# Buck_Converter.net
KiCad netlist of a schematic drawn in Altium Designer
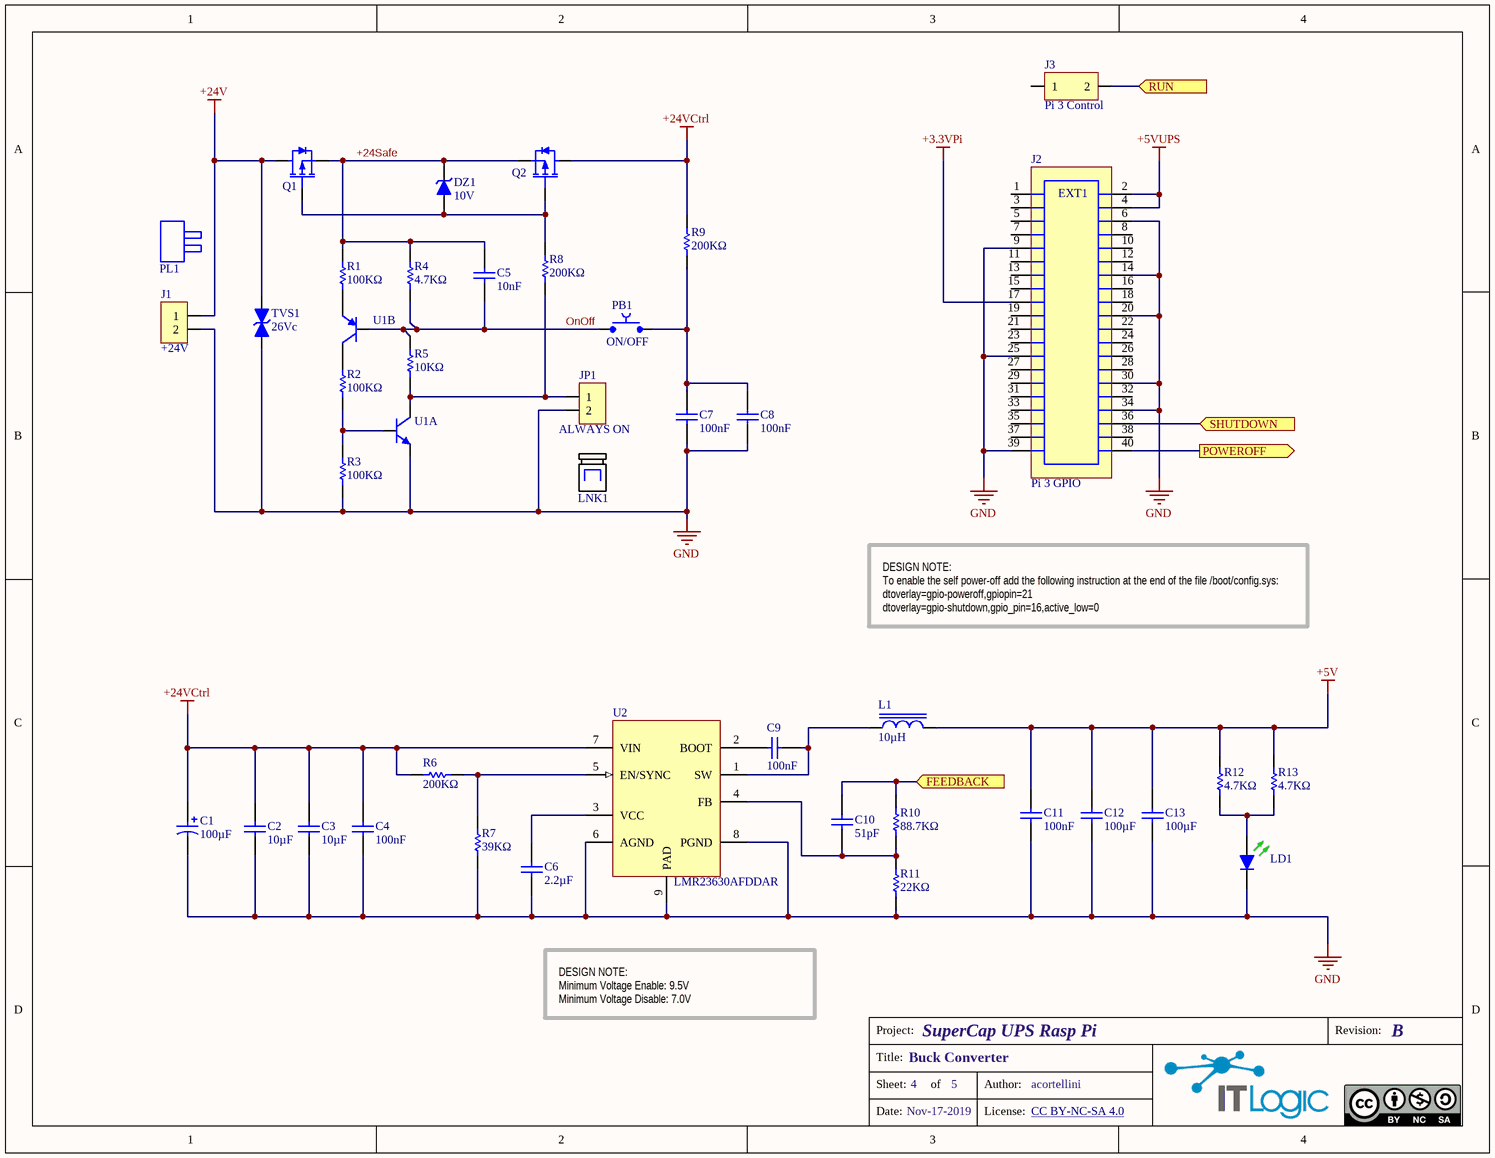
[diagram p0: Buck Converter.SchDoc]

(export (version "E")
  (design (tool "Eeschema 10.0.6"))
  (components
    (comp (ref "C1")
      (value "100µF")
      (footprint "C-AE-C6-H60")
      (description "Cap Electrolytic Alu 100uF 300V 20% (5.8 X 6.1mm) SMD 600mA 2000h 105C")
      (fields
        (field (name "MANUFACTURER") "Panasonic")
        (field (name "MANUFACTURER PART NUMBER") "EEE-FT1V101AP")
      )
      (libsource (lib "IT Logic Library") (part "EEE-FT1V101AP"))
    )
    (comp (ref "C2")
      (value "10µF")
      (footprint "C1206-H180")
      (description "Cap 1206 Case Ceramic 10uF 50V X5S 20%")
      (fields
        (field (name "MANUFACTURER") "Murata")
        (field (name "MANUFACTURER PART NUMBER") "GRT31CR61H106ME01L")
      )
      (libsource (lib "IT Logic Library") (part "GRT31CR61H106ME01L"))
    )
    (comp (ref "C3")
      (value "10µF")
      (footprint "C1206-H180")
      (description "Cap 1206 Case Ceramic 10uF 50V X5S 20%")
      (fields
        (field (name "MANUFACTURER") "Murata")
        (field (name "MANUFACTURER PART NUMBER") "GRT31CR61H106ME01L")
      )
      (libsource (lib "IT Logic Library") (part "GRT31CR61H106ME01L"))
    )
    (comp (ref "C4")
      (value "100nF")
      (footprint "C0805-H10")
      (description "Cap 0805 Case Ceramic 100nF 50V X7R")
      (fields
        (field (name "MANUFACTURER") "KEMET")
        (field (name "MANUFACTURER PART NUMBER") "C0805C104K5RACTU")
      )
      (libsource (lib "IT Logic Library") (part "C0805C104K5RACTU"))
    )
    (comp (ref "C5")
      (value "10nF")
      (footprint "C0805-H10")
      (description "Cap 0805 Case Ceramic 10nF 50V X7R")
      (fields
        (field (name "MANUFACTURER") "KEMET")
        (field (name "MANUFACTURER PART NUMBER") "C0805C103K5RACTU")
      )
      (libsource (lib "IT Logic Library") (part "C0805C103K5RACTU"))
    )
    (comp (ref "C6")
      (value "2.2µF")
      (footprint "C0805-H140")
      (description "Cap 0805 Case Ceramic 2.2uF 16V X7R 10%")
      (fields
        (field (name "MANUFACTURER") "KEMET")
        (field (name "MANUFACTURER PART NUMBER") "C0805C225K4RACTU")
      )
      (libsource (lib "IT Logic Library") (part "C0805C225K4RACTU"))
    )
    (comp (ref "C7")
      (value "100nF")
      (footprint "C0805-H10")
      (description "Cap 0805 Case Ceramic 100nF 50V X7R")
      (fields
        (field (name "MANUFACTURER") "KEMET")
        (field (name "MANUFACTURER PART NUMBER") "C0805C104K5RACTU")
      )
      (libsource (lib "IT Logic Library") (part "C0805C104K5RACTU"))
    )
    (comp (ref "C8")
      (value "100nF")
      (footprint "C0805-H10")
      (description "Cap 0805 Case Ceramic 100nF 50V X7R")
      (fields
        (field (name "MANUFACTURER") "KEMET")
        (field (name "MANUFACTURER PART NUMBER") "C0805C104K5RACTU")
      )
      (libsource (lib "IT Logic Library") (part "C0805C104K5RACTU"))
    )
    (comp (ref "C9")
      (value "100nF")
      (footprint "C0805-H10")
      (description "Cap 0805 Case Ceramic 100nF 50V X7R")
      (fields
        (field (name "MANUFACTURER") "KEMET")
        (field (name "MANUFACTURER PART NUMBER") "C0805C104K5RACTU")
      )
      (libsource (lib "IT Logic Library") (part "C0805C104K5RACTU"))
    )
    (comp (ref "C10")
      (value "51pF")
      (footprint "C0805-H10")
      (description "Cap 0805 Case Ceramic 51pF 50V C0G 10%")
      (fields
        (field (name "MANUFACTURER") "KEMET")
        (field (name "MANUFACTURER PART NUMBER") "C0805C510K5GACTU")
      )
      (libsource (lib "IT Logic Library") (part "C0805C510K5GACTU"))
    )
    (comp (ref "C11")
      (value "100nF")
      (footprint "C0805-H10")
      (description "Cap 0805 Case Ceramic 100nF 50V X7R")
      (fields
        (field (name "MANUFACTURER") "KEMET")
        (field (name "MANUFACTURER PART NUMBER") "C0805C104K5RACTU")
      )
      (libsource (lib "IT Logic Library") (part "C0805C104K5RACTU"))
    )
    (comp (ref "C12")
      (value "100µF")
      (footprint "C1210-H250")
      (description "Cap 1210 Case Ceramic 100uF 10V X5S 20%")
      (fields
        (field (name "MANUFACTURER") "Murata")
        (field (name "MANUFACTURER PART NUMBER") "GRM32ER61A107ME20L")
      )
      (libsource (lib "IT Logic Library") (part "GRM32ER61A107ME20L"))
    )
    (comp (ref "C13")
      (value "100µF")
      (footprint "C1210-H250")
      (description "Cap 1210 Case Ceramic 100uF 10V X5S 20%")
      (fields
        (field (name "MANUFACTURER") "Murata")
        (field (name "MANUFACTURER PART NUMBER") "GRM32ER61A107ME20L")
      )
      (libsource (lib "IT Logic Library") (part "GRM32ER61A107ME20L"))
    )
    (comp (ref "DZ1")
      (value "10V")
      (footprint "SOD-123")
      (description "Diode Zener Single 10V 5% 400mW SOD-123")
      (fields
        (field (name "MANUFACTURER") "Vishay Semiconductors")
        (field (name "MANUFACTURER PART NUMBER") "BZT52C10-E3-08")
      )
      (libsource (lib "IT Logic Library") (part "BZT52C10-E3-08"))
    )
    (comp (ref "EXT1")
      (value "SSQ-120-03-T-D-MEC")
      (footprint "SSQ-120-03-D-BOTTOM")
      (description "Conn Post Socket Header Vert - 2 Row - 20 Pos - 10 mm Lenght - Tin")
      (fields
        (field (name "MANUFACTURER") "Samtec")
        (field (name "MANUFACTURER PART NUMBER") "SSQ-120-03-T-D")
      )
      (libsource (lib "IT Logic Library") (part "SSQ-120-03-T-D-MEC"))
    )
    (comp (ref "J1")
      (value "+24V")
      (footprint "691322110002")
      (description "Conn Term Block Header 2 Pos 3.5 mm")
      (fields
        (field (name "MANUFACTURER") "Wurth Electronics")
        (field (name "MANUFACTURER PART NUMBER") "691322110002")
      )
      (libsource (lib "IT Logic Library") (part "691322110002"))
    )
    (comp (ref "J2")
      (value "Pi 3 GPIO")
      (footprint "HLE-120-02-F-DV-BE")
      (description "Conn Socket Header Vert - 2 Row - 20 Pos - SMD")
      (fields
        (field (name "MANUFACTURER") "Samtec")
        (field (name "MANUFACTURER PART NUMBER") "HLE-120-02-F-DV-BE")
      )
      (libsource (lib "IT Logic Library") (part "HLE-120-02-F-DV-BE"))
    )
    (comp (ref "J3")
      (value "Pi 3 Control")
      (footprint "SSQ-102-01-S-BOTTOM")
      (description "Conn Post Socket Header Vert - 1 Row - 2 Pos - 3 mm Lenght - Tin")
      (fields
        (field (name "MANUFACTURER") "Samtec")
        (field (name "MANUFACTURER PART NUMBER") "SSQ-102-01-T-S")
      )
      (libsource (lib "IT Logic Library") (part "SSQ-102-01-T-S"))
    )
    (comp (ref "JP1")
      (value "ALWAYS ON")
      (footprint "HDR-V-1R-02P-5.8L")
      (description "Breakaway Header Vert - 1 Row - 2 Pos - 6 mm Lenght - Gold")
      (fields (field (name "MANUFACTURER") "Molex") (field (name "MANUFACTURER PART NUMBER") "22-28-4023"))
      (libsource (lib "IT Logic Library") (part "22-28-4023"))
    )
    (comp (ref "L1")
      (value "10µH")
      (footprint "IND-XAL6060")
      (description "Inductor Power XAL60 Series, 10uH, 7.6A,  Shielded, 27 mOhm, SMD")
      (fields
        (field (name "MANUFACTURER") "Coilcraft")
        (field (name "MANUFACTURER PART NUMBER") "XAL6060-103MEB")
      )
      (libsource (lib "IT Logic Library") (part "XAL6060-103MEB"))
    )
    (comp (ref "LD1")
      (value "LTST-S220KGKT")
      (footprint "LED-0805-G-SIDE")
      (description "LED 0805 Side Green 569nm 2-Pin")
      (fields (field (name "MANUFACTURER") "Vishay Lite-On"))
      (libsource (lib "IT Logic Library") (part "LTST-S220KGKT"))
    )
    (comp (ref "LNK1")
      (value "2-881545-2")
      (description "Jumper Red, 2 Pos, 2.54 pitch")
      (fields (field (name "MANUFACTURER") "TE Connectivity"))
      (libsource (lib "IT Logic Library") (part "2-881545-2"))
    )
    (comp (ref "PB1")
      (value "ON/OFF")
      (footprint "BUT-1-1825027-4")
      (description "Tactile Switch, Round Stem, Color ivory, Lenght 3.55mm, Right Angle, Through Hole.")
      (fields
        (field (name "MANUFACTURER") "TE Connectivity")
        (field (name "MANUFACTURER PART NUMBER") "1-1825027-4")
      )
      (libsource (lib "IT Logic Library") (part "1-1825027-4"))
    )
    (comp (ref "PL1")
      (value "691361100002")
      (description "Conn Term Block Plug Vert 2 Pos 3.5 mm")
      (fields (field (name "MANUFACTURER") "Wurth Electronics"))
      (libsource (lib "IT Logic Library") (part "691361100002"))
    )
    (comp (ref "Q1")
      (value "DMP6023LFG")
      (footprint "PowerDI3333-8-S")
      (description "Mosfet P 60V Vds 20V Vgs 25mOhm PowerDI3333-8")
      (fields (field (name "MANUFACTURER") "Diodes Incorporated"))
      (libsource (lib "IT Logic Library") (part "DMP6023LFG"))
    )
    (comp (ref "Q2")
      (value "DMP6023LFG")
      (footprint "PowerDI3333-8-S")
      (description "Mosfet P 60V Vds 20V Vgs 25mOhm PowerDI3333-8")
      (fields (field (name "MANUFACTURER") "Diodes Incorporated"))
      (libsource (lib "IT Logic Library") (part "DMP6023LFG"))
    )
    (comp (ref "R1")
      (value "100KΩ")
      (footprint "R0805-H60")
      (description "Resistor 0805 Case 100KR 1% 1/8W")
      (fields
        (field (name "MANUFACTURER") "Yageo")
        (field (name "MANUFACTURER PART NUMBER") "RC0805FR-07100KL")
      )
      (libsource (lib "IT Logic Library") (part "RC0805FR-07100KL"))
    )
    (comp (ref "R2")
      (value "100KΩ")
      (footprint "R0805-H60")
      (description "Resistor 0805 Case 100KR 1% 1/8W")
      (fields
        (field (name "MANUFACTURER") "Yageo")
        (field (name "MANUFACTURER PART NUMBER") "RC0805FR-07100KL")
      )
      (libsource (lib "IT Logic Library") (part "RC0805FR-07100KL"))
    )
    (comp (ref "R3")
      (value "100KΩ")
      (footprint "R0805-H60")
      (description "Resistor 0805 Case 100KR 1% 1/8W")
      (fields
        (field (name "MANUFACTURER") "Yageo")
        (field (name "MANUFACTURER PART NUMBER") "RC0805FR-07100KL")
      )
      (libsource (lib "IT Logic Library") (part "RC0805FR-07100KL"))
    )
    (comp (ref "R4")
      (value "4.7KΩ")
      (footprint "R0805-H60")
      (description "Resistor 0805 Case 4.7KR 1% 1/8W")
      (fields
        (field (name "MANUFACTURER") "Yageo")
        (field (name "MANUFACTURER PART NUMBER") "RC0805FR-074K7L")
      )
      (libsource (lib "IT Logic Library") (part "RC0805FR-074K7L"))
    )
    (comp (ref "R5")
      (value "10KΩ")
      (footprint "R0805-H60")
      (description "Resistor 0805 Case 10KR 1% 1/8W")
      (fields
        (field (name "MANUFACTURER") "Yageo")
        (field (name "MANUFACTURER PART NUMBER") "RC0805FR-0710KL")
      )
      (libsource (lib "IT Logic Library") (part "RC0805FR-0710KL"))
    )
    (comp (ref "R6")
      (value "200KΩ")
      (footprint "R0805-H60")
      (description "Resistor 0805 Case 200KR 1% 1/8W")
      (fields
        (field (name "MANUFACTURER") "Yageo")
        (field (name "MANUFACTURER PART NUMBER") "RC0805FR-07200KL")
      )
      (libsource (lib "IT Logic Library") (part "RC0805FR-07200KL"))
    )
    (comp (ref "R7")
      (value "39KΩ")
      (footprint "R0805-H60")
      (description "Resistor 0805 Case 39KR 1% 1/8W")
      (fields
        (field (name "MANUFACTURER") "Yageo")
        (field (name "MANUFACTURER PART NUMBER") "RC0805FR-0739KL")
      )
      (libsource (lib "IT Logic Library") (part "RC0805FR-0739KL"))
    )
    (comp (ref "R8")
      (value "200KΩ")
      (footprint "R0805-H60")
      (description "Resistor 0805 Case 200KR 1% 1/8W")
      (fields
        (field (name "MANUFACTURER") "Yageo")
        (field (name "MANUFACTURER PART NUMBER") "RC0805FR-07200KL")
      )
      (libsource (lib "IT Logic Library") (part "RC0805FR-07200KL"))
    )
    (comp (ref "R9")
      (value "200KΩ")
      (footprint "R0805-H60")
      (description "Resistor 0805 Case 200KR 1% 1/8W")
      (fields
        (field (name "MANUFACTURER") "Yageo")
        (field (name "MANUFACTURER PART NUMBER") "RC0805FR-07200KL")
      )
      (libsource (lib "IT Logic Library") (part "RC0805FR-07200KL"))
    )
    (comp (ref "R10")
      (value "88.7KΩ")
      (footprint "R0805-H60")
      (description "Resistor 0805 Case 88.7KR 1% 1/8W")
      (fields
        (field (name "MANUFACTURER") "Yageo")
        (field (name "MANUFACTURER PART NUMBER") "RC0805FR-0788K7L")
      )
      (libsource (lib "IT Logic Library") (part "RC0805FR-0788K7L"))
    )
    (comp (ref "R11")
      (value "22KΩ")
      (footprint "R0805-H60")
      (description "Resistor 0805 Case 22KR 1% 1/8W")
      (fields
        (field (name "MANUFACTURER") "Yageo")
        (field (name "MANUFACTURER PART NUMBER") "RC0805FR-0722KL")
      )
      (libsource (lib "IT Logic Library") (part "RC0805FR-0722KL"))
    )
    (comp (ref "R12")
      (value "4.7KΩ")
      (footprint "R0805-H60")
      (description "Resistor 0805 Case 4.7KR 1% 1/8W")
      (fields
        (field (name "MANUFACTURER") "Yageo")
        (field (name "MANUFACTURER PART NUMBER") "RC0805FR-074K7L")
      )
      (libsource (lib "IT Logic Library") (part "RC0805FR-074K7L"))
    )
    (comp (ref "R13")
      (value "4.7KΩ")
      (footprint "R0805-H60")
      (description "Resistor 0805 Case 4.7KR 1% 1/8W")
      (fields
        (field (name "MANUFACTURER") "Yageo")
        (field (name "MANUFACTURER PART NUMBER") "RC0805FR-074K7L")
      )
      (libsource (lib "IT Logic Library") (part "RC0805FR-074K7L"))
    )
    (comp (ref "TVS1")
      (value "26Vc")
      (footprint "DO-214AC-SMA-NO POL")
      (description "TVS Diode Bidirectional 26Vs, 42.1Vc, 9.5 Amp, SMA")
      (fields (field (name "MANUFACTURER") "Littelfuse") (field (name "MANUFACTURER PART NUMBER") "SMAJ26CA"))
      (libsource (lib "IT Logic Library") (part "SMAJ26CA"))
    )
    (comp (ref "U1")
      (value "MBT3946DW1T1G")
      (footprint "SOT-363")
      (description "Transistor Complementary Dual 40V  200mA SOT−363")
      (fields (field (name "MANUFACTURER") "ON Semiconductor"))
      (libsource (lib "IT Logic Library") (part "MBT3946DW1T1G"))
    )
    (comp (ref "U2")
      (value "LMR23630AFDDAR")
      (footprint "SOIC-8-N-HT")
      (description "Conv DC-DC Sync Step-Down 36V 3A 9-Pin(8+Pab) HSOIC-8")
      (fields (field (name "MANUFACTURER") "Texas Instruments"))
      (libsource (lib "IT Logic Library") (part "LMR23630AFDDAR"))
    )
  )
  (nets
    (net (code "1") (name "+3.3VPi") (class "Default")
      (node (ref "J2") (pin "17") (pinfunction "17_17") (pintype "passive"))
    )
    (net (code "2") (name "+5V") (class "Default")
      (node (ref "C11") (pin "2") (pinfunction "2_2") (pintype "passive"))
      (node (ref "C12") (pin "2") (pinfunction "2_2") (pintype "passive"))
      (node (ref "C13") (pin "2") (pinfunction "2_2") (pintype "passive"))
      (node (ref "L1") (pin "2") (pinfunction "2_2") (pintype "passive"))
      (node (ref "R12") (pin "2") (pinfunction "2_2") (pintype "passive"))
      (node (ref "R13") (pin "2") (pinfunction "2_2") (pintype "passive"))
    )
    (net (code "3") (name "+5VUPS") (class "Default")
      (node (ref "J2") (pin "2") (pinfunction "2_2") (pintype "passive"))
      (node (ref "J2") (pin "4") (pinfunction "4_4") (pintype "passive"))
    )
    (net (code "4") (name "+24V") (class "Default")
      (node (ref "J1") (pin "1") (pinfunction "1_1") (pintype "passive"))
      (node (ref "Q1") (pin "3") (pinfunction "D_3") (pintype "passive"))
      (node (ref "TVS1") (pin "2") (pinfunction "2_2") (pintype "passive"))
    )
    (net (code "5") (name "+24VCtrl") (class "Default")
      (node (ref "C1") (pin "1") (pinfunction "1_1") (pintype "passive"))
      (node (ref "C2") (pin "2") (pinfunction "2_2") (pintype "passive"))
      (node (ref "C3") (pin "2") (pinfunction "2_2") (pintype "passive"))
      (node (ref "C4") (pin "2") (pinfunction "2_2") (pintype "passive"))
      (node (ref "Q2") (pin "3") (pinfunction "D_3") (pintype "passive"))
      (node (ref "R6") (pin "2") (pinfunction "2_2") (pintype "passive"))
      (node (ref "R9") (pin "2") (pinfunction "2_2") (pintype "passive"))
      (node (ref "U2") (pin "7") (pinfunction "VIN_7") (pintype "power_in"))
    )
    (net (code "6") (name "/+24Safe") (class "Default")
      (node (ref "C5") (pin "2") (pinfunction "2_2") (pintype "passive"))
      (node (ref "DZ1") (pin "1") (pinfunction "K_1") (pintype "passive"))
      (node (ref "Q1") (pin "1") (pinfunction "S_1") (pintype "passive"))
      (node (ref "Q2") (pin "1") (pinfunction "S_1") (pintype "passive"))
      (node (ref "R1") (pin "1") (pinfunction "1_1") (pintype "passive"))
      (node (ref "R4") (pin "2") (pinfunction "2_2") (pintype "passive"))
    )
    (net (code "7") (name "/FEEDBACK") (class "Default")
      (node (ref "C10") (pin "2") (pinfunction "2_2") (pintype "passive"))
      (node (ref "R10") (pin "2") (pinfunction "2_2") (pintype "passive"))
    )
    (net (code "8") (name "/OnOff") (class "Default")
      (node (ref "C5") (pin "1") (pinfunction "1_1") (pintype "passive"))
      (node (ref "PB1") (pin "1") (pinfunction "1_1") (pintype "passive"))
      (node (ref "R4") (pin "1") (pinfunction "1_1") (pintype "passive"))
      (node (ref "R5") (pin "1") (pinfunction "1_1") (pintype "passive"))
      (node (ref "U1") (pin "5") (pinfunction "B_5") (pintype "passive"))
    )
    (net (code "9") (name "/POWEROFF") (class "Default")
      (node (ref "J2") (pin "40") (pinfunction "40_40") (pintype "passive"))
    )
    (net (code "10") (name "/RUN") (class "Default")
      (node (ref "J3") (pin "2") (pinfunction "2_2") (pintype "passive"))
    )
    (net (code "11") (name "/SHUTDOWN") (class "Default")
      (node (ref "J2") (pin "36") (pinfunction "36_36") (pintype "passive"))
    )
    (net (code "12") (name "GND") (class "Default")
      (node (ref "C1") (pin "2") (pinfunction "2_2") (pintype "passive"))
      (node (ref "C11") (pin "1") (pinfunction "1_1") (pintype "passive"))
      (node (ref "C12") (pin "1") (pinfunction "1_1") (pintype "passive"))
      (node (ref "C13") (pin "1") (pinfunction "1_1") (pintype "passive"))
      (node (ref "C2") (pin "1") (pinfunction "1_1") (pintype "passive"))
      (node (ref "C3") (pin "1") (pinfunction "1_1") (pintype "passive"))
      (node (ref "C4") (pin "1") (pinfunction "1_1") (pintype "passive"))
      (node (ref "C6") (pin "1") (pinfunction "1_1") (pintype "passive"))
      (node (ref "C7") (pin "1") (pinfunction "1_1") (pintype "passive"))
      (node (ref "C8") (pin "1") (pinfunction "1_1") (pintype "passive"))
      (node (ref "J1") (pin "2") (pinfunction "2_2") (pintype "passive"))
      (node (ref "J2") (pin "14") (pinfunction "14_14") (pintype "passive"))
      (node (ref "J2") (pin "20") (pinfunction "20_20") (pintype "passive"))
      (node (ref "J2") (pin "25") (pinfunction "25_25") (pintype "passive"))
      (node (ref "J2") (pin "30") (pinfunction "30_30") (pintype "passive"))
      (node (ref "J2") (pin "34") (pinfunction "34_34") (pintype "passive"))
      (node (ref "J2") (pin "39") (pinfunction "39_39") (pintype "passive"))
      (node (ref "J2") (pin "6") (pinfunction "6_6") (pintype "passive"))
      (node (ref "J2") (pin "9") (pinfunction "9_9") (pintype "passive"))
      (node (ref "JP1") (pin "2") (pinfunction "2_2") (pintype "passive"))
      (node (ref "LD1") (pin "1") (pinfunction "K_1") (pintype "passive"))
      (node (ref "R11") (pin "1") (pinfunction "1_1") (pintype "passive"))
      (node (ref "R3") (pin "1") (pinfunction "1_1") (pintype "passive"))
      (node (ref "R7") (pin "1") (pinfunction "1_1") (pintype "passive"))
      (node (ref "TVS1") (pin "1") (pinfunction "1_1") (pintype "passive"))
      (node (ref "U1") (pin "1") (pinfunction "E_1") (pintype "passive"))
      (node (ref "U2") (pin "6") (pinfunction "AGND_6") (pintype "power_in"))
      (node (ref "U2") (pin "8") (pinfunction "PGND_8") (pintype "power_in"))
      (node (ref "U2") (pin "9") (pinfunction "PAD_9") (pintype "power_in"))
    )
    (net (code "13") (name "Net-(C7-Pad2)") (class "Default")
      (node (ref "C7") (pin "2") (pinfunction "2_2") (pintype "passive"))
      (node (ref "C8") (pin "2") (pinfunction "2_2") (pintype "passive"))
      (node (ref "PB1") (pin "2") (pinfunction "2_2") (pintype "passive"))
      (node (ref "R9") (pin "1") (pinfunction "1_1") (pintype "passive"))
    )
    (net (code "14") (name "Net-(DZ1-A)") (class "Default")
      (node (ref "DZ1") (pin "2") (pinfunction "A_2") (pintype "passive"))
      (node (ref "Q1") (pin "2") (pinfunction "G_2") (pintype "passive"))
      (node (ref "Q2") (pin "2") (pinfunction "G_2") (pintype "passive"))
      (node (ref "R8") (pin "2") (pinfunction "2_2") (pintype "passive"))
    )
    (net (code "15") (name "Net-(LD1-A)") (class "Default")
      (node (ref "LD1") (pin "2") (pinfunction "A_2") (pintype "passive"))
      (node (ref "R12") (pin "1") (pinfunction "1_1") (pintype "passive"))
      (node (ref "R13") (pin "1") (pinfunction "1_1") (pintype "passive"))
    )
    (net (code "16") (name "Net-(U1A-B)") (class "Default")
      (node (ref "R2") (pin "1") (pinfunction "1_1") (pintype "passive"))
      (node (ref "R3") (pin "2") (pinfunction "2_2") (pintype "passive"))
      (node (ref "U1") (pin "2") (pinfunction "B_2") (pintype "passive"))
    )
    (net (code "17") (name "Net-(U1A-C)") (class "Default")
      (node (ref "JP1") (pin "1") (pinfunction "1_1") (pintype "passive"))
      (node (ref "R5") (pin "2") (pinfunction "2_2") (pintype "passive"))
      (node (ref "R8") (pin "1") (pinfunction "1_1") (pintype "passive"))
      (node (ref "U1") (pin "6") (pinfunction "C_6") (pintype "passive"))
    )
    (net (code "18") (name "Net-(U1B-C)") (class "Default")
      (node (ref "R2") (pin "2") (pinfunction "2_2") (pintype "passive"))
      (node (ref "U1") (pin "3") (pinfunction "C_3") (pintype "passive"))
    )
    (net (code "19") (name "Net-(U1B-E)") (class "Default")
      (node (ref "R1") (pin "2") (pinfunction "2_2") (pintype "passive"))
      (node (ref "U1") (pin "4") (pinfunction "E_4") (pintype "passive"))
    )
    (net (code "20") (name "Net-(U2-BOOT)") (class "Default")
      (node (ref "C9") (pin "1") (pinfunction "1_1") (pintype "passive"))
      (node (ref "U2") (pin "2") (pinfunction "BOOT_2") (pintype "power_in"))
    )
    (net (code "21") (name "Net-(U2-EN{slash}SYNC)") (class "Default")
      (node (ref "R6") (pin "1") (pinfunction "1_1") (pintype "passive"))
      (node (ref "R7") (pin "2") (pinfunction "2_2") (pintype "passive"))
      (node (ref "U2") (pin "5") (pinfunction "EN/SYNC_5") (pintype "input"))
    )
    (net (code "22") (name "Net-(U2-FB)") (class "Default")
      (node (ref "C10") (pin "1") (pinfunction "1_1") (pintype "passive"))
      (node (ref "R10") (pin "1") (pinfunction "1_1") (pintype "passive"))
      (node (ref "R11") (pin "2") (pinfunction "2_2") (pintype "passive"))
      (node (ref "U2") (pin "4") (pinfunction "FB_4") (pintype "power_in"))
    )
    (net (code "23") (name "Net-(U2-SW)") (class "Default")
      (node (ref "C9") (pin "2") (pinfunction "2_2") (pintype "passive"))
      (node (ref "L1") (pin "1") (pinfunction "1_1") (pintype "passive"))
      (node (ref "U2") (pin "1") (pinfunction "SW_1") (pintype "power_in"))
    )
    (net (code "24") (name "Net-(U2-VCC)") (class "Default")
      (node (ref "C6") (pin "2") (pinfunction "2_2") (pintype "passive"))
      (node (ref "U2") (pin "3") (pinfunction "VCC_3") (pintype "power_in"))
    )
    (net (code "25") (name "unconnected-(J2-Pad1)") (class "Default")
      (node (ref "J2") (pin "1") (pinfunction "1_1") (pintype "passive"))
    )
    (net (code "26") (name "unconnected-(J2-Pad3)") (class "Default")
      (node (ref "J2") (pin "3") (pinfunction "3_3") (pintype "passive"))
    )
    (net (code "27") (name "unconnected-(J2-Pad5)") (class "Default")
      (node (ref "J2") (pin "5") (pinfunction "5_5") (pintype "passive"))
    )
    (net (code "28") (name "unconnected-(J2-Pad7)") (class "Default")
      (node (ref "J2") (pin "7") (pinfunction "7_7") (pintype "passive"))
    )
    (net (code "29") (name "unconnected-(J2-Pad8)") (class "Default")
      (node (ref "J2") (pin "8") (pinfunction "8_8") (pintype "passive"))
    )
    (net (code "30") (name "unconnected-(J2-Pad10)") (class "Default")
      (node (ref "J2") (pin "10") (pinfunction "10_10") (pintype "passive"))
    )
    (net (code "31") (name "unconnected-(J2-Pad11)") (class "Default")
      (node (ref "J2") (pin "11") (pinfunction "11_11") (pintype "passive"))
    )
    (net (code "32") (name "unconnected-(J2-Pad12)") (class "Default")
      (node (ref "J2") (pin "12") (pinfunction "12_12") (pintype "passive"))
    )
    (net (code "33") (name "unconnected-(J2-Pad13)") (class "Default")
      (node (ref "J2") (pin "13") (pinfunction "13_13") (pintype "passive"))
    )
    (net (code "34") (name "unconnected-(J2-Pad15)") (class "Default")
      (node (ref "J2") (pin "15") (pinfunction "15_15") (pintype "passive"))
    )
    (net (code "35") (name "unconnected-(J2-Pad16)") (class "Default")
      (node (ref "J2") (pin "16") (pinfunction "16_16") (pintype "passive"))
    )
    (net (code "36") (name "unconnected-(J2-Pad18)") (class "Default")
      (node (ref "J2") (pin "18") (pinfunction "18_18") (pintype "passive"))
    )
    (net (code "37") (name "unconnected-(J2-Pad19)") (class "Default")
      (node (ref "J2") (pin "19") (pinfunction "19_19") (pintype "passive"))
    )
    (net (code "38") (name "unconnected-(J2-Pad21)") (class "Default")
      (node (ref "J2") (pin "21") (pinfunction "21_21") (pintype "passive"))
    )
    (net (code "39") (name "unconnected-(J2-Pad22)") (class "Default")
      (node (ref "J2") (pin "22") (pinfunction "22_22") (pintype "passive"))
    )
    (net (code "40") (name "unconnected-(J2-Pad23)") (class "Default")
      (node (ref "J2") (pin "23") (pinfunction "23_23") (pintype "passive"))
    )
    (net (code "41") (name "unconnected-(J2-Pad24)") (class "Default")
      (node (ref "J2") (pin "24") (pinfunction "24_24") (pintype "passive"))
    )
    (net (code "42") (name "unconnected-(J2-Pad26)") (class "Default")
      (node (ref "J2") (pin "26") (pinfunction "26_26") (pintype "passive"))
    )
    (net (code "43") (name "unconnected-(J2-Pad27)") (class "Default")
      (node (ref "J2") (pin "27") (pinfunction "27_27") (pintype "passive"))
    )
    (net (code "44") (name "unconnected-(J2-Pad28)") (class "Default")
      (node (ref "J2") (pin "28") (pinfunction "28_28") (pintype "passive"))
    )
    (net (code "45") (name "unconnected-(J2-Pad29)") (class "Default")
      (node (ref "J2") (pin "29") (pinfunction "29_29") (pintype "passive"))
    )
    (net (code "46") (name "unconnected-(J2-Pad31)") (class "Default")
      (node (ref "J2") (pin "31") (pinfunction "31_31") (pintype "passive"))
    )
    (net (code "47") (name "unconnected-(J2-Pad32)") (class "Default")
      (node (ref "J2") (pin "32") (pinfunction "32_32") (pintype "passive"))
    )
    (net (code "48") (name "unconnected-(J2-Pad33)") (class "Default")
      (node (ref "J2") (pin "33") (pinfunction "33_33") (pintype "passive"))
    )
    (net (code "49") (name "unconnected-(J2-Pad35)") (class "Default")
      (node (ref "J2") (pin "35") (pinfunction "35_35") (pintype "passive"))
    )
    (net (code "50") (name "unconnected-(J2-Pad37)") (class "Default")
      (node (ref "J2") (pin "37") (pinfunction "37_37") (pintype "passive"))
    )
    (net (code "51") (name "unconnected-(J2-Pad38)") (class "Default")
      (node (ref "J2") (pin "38") (pinfunction "38_38") (pintype "passive"))
    )
    (net (code "52") (name "unconnected-(J3-Pad1)") (class "Default")
      (node (ref "J3") (pin "1") (pinfunction "1_1") (pintype "passive"))
    )
  )
)
